# 01SignalDetect.net
KiCad netlist of a schematic drawn in Altium Designer
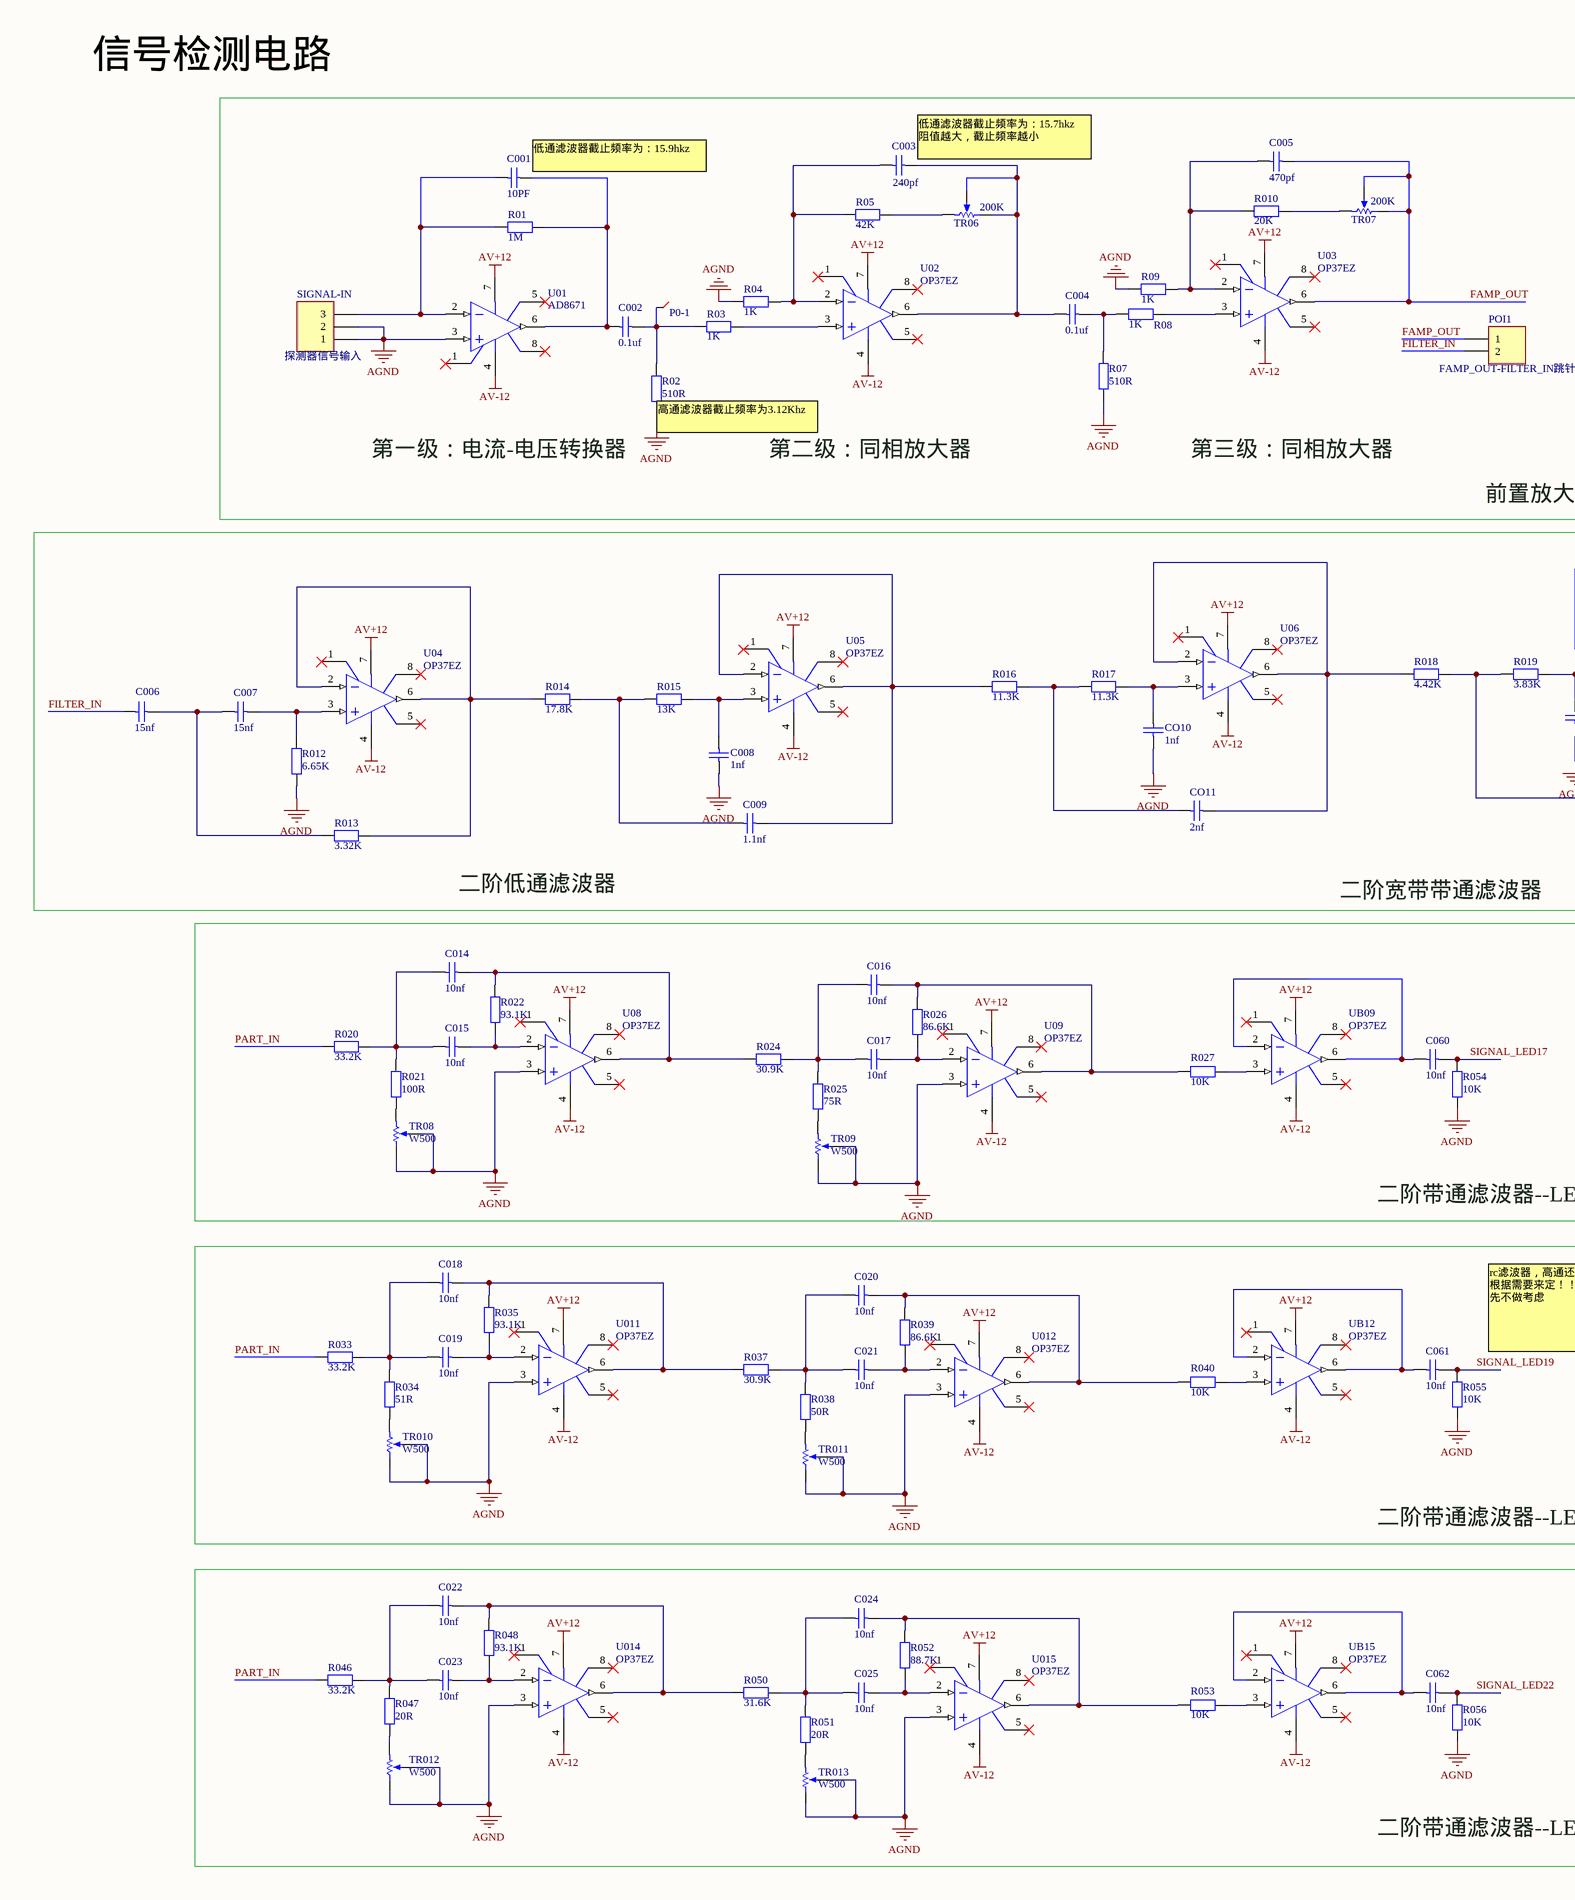
[diagram p0: 01SignalDetect.SchDoc, left]
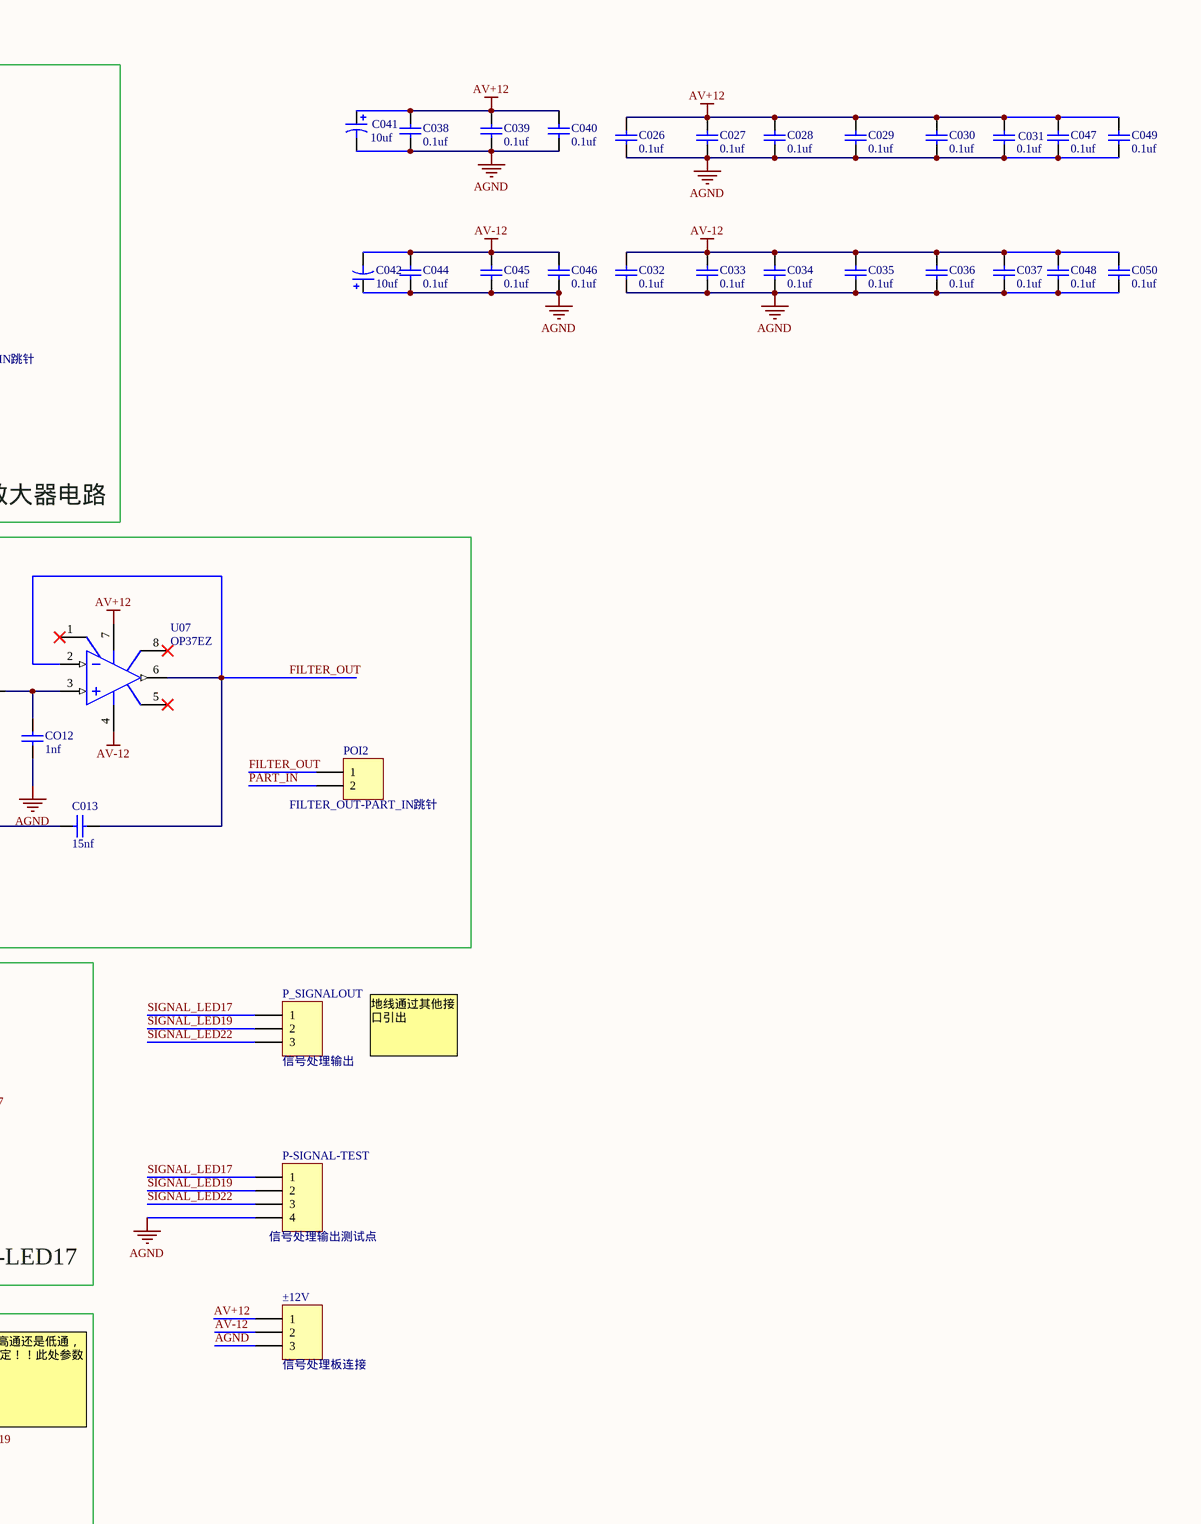
[diagram p1: 01SignalDetect.SchDoc, right]

(export (version "E")
  (design (tool "Eeschema 10.0.6"))
  (components
    (comp (ref "C001")
      (value "10PF")
      (footprint "CC0805")
      (description "Capacitor")
      (fields (field (name "Comment") "Cap") (field (name "PUBLISHER") "Altium Limited"))
      (libsource (lib "Miscellaneous Devices") (part "Cap"))
    )
    (comp (ref "C002")
      (value "0.1uf")
      (footprint "CC0805")
      (description "Capacitor")
      (fields (field (name "Comment") "Cap") (field (name "PUBLISHER") "Altium Limited"))
      (libsource (lib "Miscellaneous Devices") (part "Cap"))
    )
    (comp (ref "C003")
      (value "240pf")
      (footprint "CC0805")
      (description "Capacitor")
      (fields (field (name "Comment") "Cap") (field (name "PUBLISHER") "Altium Limited"))
      (libsource (lib "Miscellaneous Devices") (part "Cap"))
    )
    (comp (ref "C004")
      (value "0.1uf")
      (footprint "CC0805")
      (description "Capacitor")
      (fields (field (name "Comment") "Cap") (field (name "PUBLISHER") "Altium Limited"))
      (libsource (lib "Miscellaneous Devices") (part "Cap"))
    )
    (comp (ref "C005")
      (value "470pf")
      (footprint "CC0805")
      (description "Capacitor")
      (fields (field (name "Comment") "Cap") (field (name "PUBLISHER") "Altium Limited"))
      (libsource (lib "Miscellaneous Devices") (part "Cap"))
    )
    (comp (ref "C006")
      (value "15nf")
      (footprint "CC0805")
      (description "Capacitor")
      (fields (field (name "Comment") "Cap") (field (name "PUBLISHER") "Altium Limited"))
      (libsource (lib "Miscellaneous Devices") (part "Cap"))
    )
    (comp (ref "C007")
      (value "15nf")
      (footprint "CC0805")
      (description "Capacitor")
      (fields (field (name "Comment") "Cap") (field (name "PUBLISHER") "Altium Limited"))
      (libsource (lib "Miscellaneous Devices") (part "Cap"))
    )
    (comp (ref "C008")
      (value "1nf")
      (footprint "CC0805")
      (description "Capacitor")
      (fields (field (name "Comment") "Cap") (field (name "PUBLISHER") "Altium Limited"))
      (libsource (lib "Miscellaneous Devices") (part "Cap"))
    )
    (comp (ref "C009")
      (value "1.1nf")
      (footprint "CC0805")
      (description "Capacitor")
      (fields (field (name "Comment") "Cap") (field (name "PUBLISHER") "Altium Limited"))
      (libsource (lib "Miscellaneous Devices") (part "Cap"))
    )
    (comp (ref "C013")
      (value "15nf")
      (footprint "CC0805")
      (description "Capacitor")
      (fields (field (name "Comment") "Cap") (field (name "PUBLISHER") "Altium Limited"))
      (libsource (lib "Miscellaneous Devices") (part "Cap"))
    )
    (comp (ref "C014")
      (value "10nf")
      (footprint "校正电容")
      (description "Capacitor")
      (fields (field (name "Comment") "Cap") (field (name "PUBLISHER") "Altium Limited"))
      (libsource (lib "Miscellaneous Devices") (part "Cap"))
    )
    (comp (ref "C015")
      (value "10nf")
      (footprint "校正电容")
      (description "Capacitor")
      (fields (field (name "Comment") "Cap") (field (name "PUBLISHER") "Altium Limited"))
      (libsource (lib "Miscellaneous Devices") (part "Cap"))
    )
    (comp (ref "C016")
      (value "10nf")
      (footprint "校正电容")
      (description "Capacitor")
      (fields (field (name "Comment") "Cap") (field (name "PUBLISHER") "Altium Limited"))
      (libsource (lib "Miscellaneous Devices") (part "Cap"))
    )
    (comp (ref "C017")
      (value "10nf")
      (footprint "校正电容")
      (description "Capacitor")
      (fields (field (name "Comment") "Cap") (field (name "PUBLISHER") "Altium Limited"))
      (libsource (lib "Miscellaneous Devices") (part "Cap"))
    )
    (comp (ref "C018")
      (value "10nf")
      (footprint "校正电容")
      (description "Capacitor")
      (fields (field (name "Comment") "Cap") (field (name "PUBLISHER") "Altium Limited"))
      (libsource (lib "Miscellaneous Devices") (part "Cap"))
    )
    (comp (ref "C019")
      (value "10nf")
      (footprint "校正电容")
      (description "Capacitor")
      (fields (field (name "Comment") "Cap") (field (name "PUBLISHER") "Altium Limited"))
      (libsource (lib "Miscellaneous Devices") (part "Cap"))
    )
    (comp (ref "C020")
      (value "10nf")
      (footprint "校正电容")
      (description "Capacitor")
      (fields (field (name "Comment") "Cap") (field (name "PUBLISHER") "Altium Limited"))
      (libsource (lib "Miscellaneous Devices") (part "Cap"))
    )
    (comp (ref "C021")
      (value "10nf")
      (footprint "校正电容")
      (description "Capacitor")
      (fields (field (name "Comment") "Cap") (field (name "PUBLISHER") "Altium Limited"))
      (libsource (lib "Miscellaneous Devices") (part "Cap"))
    )
    (comp (ref "C022")
      (value "10nf")
      (footprint "校正电容")
      (description "Capacitor")
      (fields (field (name "Comment") "Cap") (field (name "PUBLISHER") "Altium Limited"))
      (libsource (lib "Miscellaneous Devices") (part "Cap"))
    )
    (comp (ref "C023")
      (value "10nf")
      (footprint "校正电容")
      (description "Capacitor")
      (fields (field (name "Comment") "Cap") (field (name "PUBLISHER") "Altium Limited"))
      (libsource (lib "Miscellaneous Devices") (part "Cap"))
    )
    (comp (ref "C024")
      (value "10nf")
      (footprint "校正电容")
      (description "Capacitor")
      (fields (field (name "Comment") "Cap") (field (name "PUBLISHER") "Altium Limited"))
      (libsource (lib "Miscellaneous Devices") (part "Cap"))
    )
    (comp (ref "C025")
      (value "10nf")
      (footprint "校正电容")
      (description "Capacitor")
      (fields (field (name "Comment") "Cap") (field (name "PUBLISHER") "Altium Limited"))
      (libsource (lib "Miscellaneous Devices") (part "Cap"))
    )
    (comp (ref "C026")
      (value "0.1uf")
      (footprint "CC0805")
      (description "Capacitor")
      (fields (field (name "Comment") "Cap") (field (name "PUBLISHER") "Altium Limited"))
      (libsource (lib "Miscellaneous Devices") (part "Cap"))
    )
    (comp (ref "C027")
      (value "0.1uf")
      (footprint "CC0805")
      (description "Capacitor")
      (fields (field (name "Comment") "Cap") (field (name "PUBLISHER") "Altium Limited"))
      (libsource (lib "Miscellaneous Devices") (part "Cap"))
    )
    (comp (ref "C028")
      (value "0.1uf")
      (footprint "CC0805")
      (description "Capacitor")
      (fields (field (name "Comment") "Cap") (field (name "PUBLISHER") "Altium Limited"))
      (libsource (lib "Miscellaneous Devices") (part "Cap"))
    )
    (comp (ref "C029")
      (value "0.1uf")
      (footprint "CC0805")
      (description "Capacitor")
      (fields (field (name "Comment") "Cap") (field (name "PUBLISHER") "Altium Limited"))
      (libsource (lib "Miscellaneous Devices") (part "Cap"))
    )
    (comp (ref "C030")
      (value "0.1uf")
      (footprint "CC0805")
      (description "Capacitor")
      (fields (field (name "Comment") "Cap") (field (name "PUBLISHER") "Altium Limited"))
      (libsource (lib "Miscellaneous Devices") (part "Cap"))
    )
    (comp (ref "C031")
      (value "0.1uf")
      (footprint "CC0805")
      (description "Capacitor")
      (fields (field (name "Comment") "Cap") (field (name "PUBLISHER") "Altium Limited"))
      (libsource (lib "Miscellaneous Devices") (part "Cap"))
    )
    (comp (ref "C032")
      (value "0.1uf")
      (footprint "CC0805")
      (description "Capacitor")
      (fields (field (name "Comment") "Cap") (field (name "PUBLISHER") "Altium Limited"))
      (libsource (lib "Miscellaneous Devices") (part "Cap"))
    )
    (comp (ref "C033")
      (value "0.1uf")
      (footprint "CC0805")
      (description "Capacitor")
      (fields (field (name "Comment") "Cap") (field (name "PUBLISHER") "Altium Limited"))
      (libsource (lib "Miscellaneous Devices") (part "Cap"))
    )
    (comp (ref "C034")
      (value "0.1uf")
      (footprint "CC0805")
      (description "Capacitor")
      (fields (field (name "Comment") "Cap") (field (name "PUBLISHER") "Altium Limited"))
      (libsource (lib "Miscellaneous Devices") (part "Cap"))
    )
    (comp (ref "C035")
      (value "0.1uf")
      (footprint "CC0805")
      (description "Capacitor")
      (fields (field (name "Comment") "Cap") (field (name "PUBLISHER") "Altium Limited"))
      (libsource (lib "Miscellaneous Devices") (part "Cap"))
    )
    (comp (ref "C036")
      (value "0.1uf")
      (footprint "CC0805")
      (description "Capacitor")
      (fields (field (name "Comment") "Cap") (field (name "PUBLISHER") "Altium Limited"))
      (libsource (lib "Miscellaneous Devices") (part "Cap"))
    )
    (comp (ref "C037")
      (value "0.1uf")
      (footprint "CC0805")
      (description "Capacitor")
      (fields (field (name "Comment") "Cap") (field (name "PUBLISHER") "Altium Limited"))
      (libsource (lib "Miscellaneous Devices") (part "Cap"))
    )
    (comp (ref "C038")
      (value "0.1uf")
      (footprint "CC0805")
      (description "Capacitor")
      (fields (field (name "Comment") "Cap") (field (name "PUBLISHER") "Altium Limited"))
      (libsource (lib "Miscellaneous Devices") (part "Cap"))
    )
    (comp (ref "C039")
      (value "0.1uf")
      (footprint "CC0805")
      (description "Capacitor")
      (fields (field (name "Comment") "Cap") (field (name "PUBLISHER") "Altium Limited"))
      (libsource (lib "Miscellaneous Devices") (part "Cap"))
    )
    (comp (ref "C040")
      (value "0.1uf")
      (footprint "CC0805")
      (description "Capacitor")
      (fields (field (name "Comment") "Cap") (field (name "PUBLISHER") "Altium Limited"))
      (libsource (lib "Miscellaneous Devices") (part "Cap"))
    )
    (comp (ref "C041")
      (value "10uf")
      (footprint "4*4.5 贴片电解电容")
      (description "Polarized Capacitor (Radial)")
      (fields (field (name "Comment") "Cap Pol1") (field (name "PUBLISHER") "Altium Limited"))
      (libsource (lib "Miscellaneous Devices") (part "Cap Pol1"))
    )
    (comp (ref "C042")
      (value "10uf")
      (footprint "4*4.5 贴片电解电容")
      (description "Polarized Capacitor (Radial)")
      (fields (field (name "Comment") "Cap Pol1") (field (name "PUBLISHER") "Altium Limited"))
      (libsource (lib "Miscellaneous Devices") (part "Cap Pol1"))
    )
    (comp (ref "C044")
      (value "0.1uf")
      (footprint "CC0805")
      (description "Capacitor")
      (fields (field (name "Comment") "Cap") (field (name "PUBLISHER") "Altium Limited"))
      (libsource (lib "Miscellaneous Devices") (part "Cap"))
    )
    (comp (ref "C045")
      (value "0.1uf")
      (footprint "CC0805")
      (description "Capacitor")
      (fields (field (name "Comment") "Cap") (field (name "PUBLISHER") "Altium Limited"))
      (libsource (lib "Miscellaneous Devices") (part "Cap"))
    )
    (comp (ref "C046")
      (value "0.1uf")
      (footprint "CC0805")
      (description "Capacitor")
      (fields (field (name "Comment") "Cap") (field (name "PUBLISHER") "Altium Limited"))
      (libsource (lib "Miscellaneous Devices") (part "Cap"))
    )
    (comp (ref "C047")
      (value "0.1uf")
      (footprint "CC0805")
      (description "Capacitor")
      (fields (field (name "Comment") "Cap") (field (name "PUBLISHER") "Altium Limited"))
      (libsource (lib "Miscellaneous Devices") (part "Cap"))
    )
    (comp (ref "C048")
      (value "0.1uf")
      (footprint "CC0805")
      (description "Capacitor")
      (fields (field (name "Comment") "Cap") (field (name "PUBLISHER") "Altium Limited"))
      (libsource (lib "Miscellaneous Devices") (part "Cap"))
    )
    (comp (ref "C049")
      (value "0.1uf")
      (footprint "CC0805")
      (description "Capacitor")
      (fields (field (name "Comment") "Cap") (field (name "PUBLISHER") "Altium Limited"))
      (libsource (lib "Miscellaneous Devices") (part "Cap"))
    )
    (comp (ref "C050")
      (value "0.1uf")
      (footprint "CC0805")
      (description "Capacitor")
      (fields (field (name "Comment") "Cap") (field (name "PUBLISHER") "Altium Limited"))
      (libsource (lib "Miscellaneous Devices") (part "Cap"))
    )
    (comp (ref "C060")
      (value "10nf")
      (footprint "CC0805")
      (description "Capacitor")
      (fields (field (name "Comment") "Cap") (field (name "PUBLISHER") "Altium Limited"))
      (libsource (lib "Miscellaneous Devices") (part "Cap"))
    )
    (comp (ref "C061")
      (value "10nf")
      (footprint "CC0805")
      (description "Capacitor")
      (fields (field (name "Comment") "Cap") (field (name "PUBLISHER") "Altium Limited"))
      (libsource (lib "Miscellaneous Devices") (part "Cap"))
    )
    (comp (ref "C062")
      (value "10nf")
      (footprint "CC0805")
      (description "Capacitor")
      (fields (field (name "Comment") "Cap") (field (name "PUBLISHER") "Altium Limited"))
      (libsource (lib "Miscellaneous Devices") (part "Cap"))
    )
    (comp (ref "CO10")
      (value "1nf")
      (footprint "CC0805")
      (description "Capacitor")
      (fields (field (name "Comment") "Cap") (field (name "PUBLISHER") "Altium Limited"))
      (libsource (lib "Miscellaneous Devices") (part "Cap"))
    )
    (comp (ref "CO11")
      (value "2nf")
      (footprint "CC0805")
      (description "Capacitor")
      (fields (field (name "Comment") "Cap") (field (name "PUBLISHER") "Altium Limited"))
      (libsource (lib "Miscellaneous Devices") (part "Cap"))
    )
    (comp (ref "CO12")
      (value "1nf")
      (footprint "CC0805")
      (description "Capacitor")
      (fields (field (name "Comment") "Cap") (field (name "PUBLISHER") "Altium Limited"))
      (libsource (lib "Miscellaneous Devices") (part "Cap"))
    )
    (comp (ref "P-SIGNAL-TEST")
      (value "信号处理输出测试点")
      (footprint "HDR1X4")
      (description "Header, 4-Pin")
      (fields (field (name "PUBLISHER") "Altium Limited"))
      (libsource (lib "Miscellaneous Connectors") (part "Header 4"))
    )
    (comp (ref "P0-1") (value "测试点") (footprint "Text_PAD") (libsource (lib "MY device0") (part "测试点")))
    (comp (ref "POI1")
      (value "FAMP_OUT-FILTER_IN跳针")
      (footprint "HDR1X2")
      (description "Header, 2-Pin")
      (fields (field (name "PUBLISHER") "Altium Limited"))
      (libsource (lib "Miscellaneous Connectors") (part "Header 2"))
    )
    (comp (ref "POI2")
      (value "FILTER_OUT-PART_IN跳针")
      (footprint "HDR1X2")
      (description "Header, 2-Pin")
      (fields (field (name "PUBLISHER") "Altium Limited"))
      (libsource (lib "Miscellaneous Connectors") (part "Header 2"))
    )
    (comp (ref "P_SIGNALOUT")
      (value "信号处理输出")
      (footprint "HDR1X3H")
      (description "Header, 3-Pin, Right Angle")
      (fields (field (name "PUBLISHER") "Altium Limited"))
      (libsource (lib "Miscellaneous Connectors") (part "Header 3H"))
    )
    (comp (ref "R01")
      (value "1M")
      (footprint "AXIAL-0.4")
      (description "Resistor")
      (fields (field (name "Comment") "Res2") (field (name "PUBLISHER") "Altium Limited"))
      (libsource (lib "") (part "Res2_1"))
    )
    (comp (ref "R02")
      (value "510R")
      (footprint "0805")
      (description "Resistor")
      (fields (field (name "Comment") "Res2") (field (name "PUBLISHER") "Altium Limited"))
      (libsource (lib "") (part "Res2_2"))
    )
    (comp (ref "R03")
      (value "1K")
      (footprint "0805")
      (description "Resistor")
      (fields (field (name "Comment") "Res2") (field (name "PUBLISHER") "Altium Limited"))
      (libsource (lib "") (part "Res2_1"))
    )
    (comp (ref "R04")
      (value "1K")
      (footprint "0805")
      (description "Resistor")
      (fields (field (name "Comment") "Res2") (field (name "PUBLISHER") "Altium Limited"))
      (libsource (lib "") (part "Res2_1"))
    )
    (comp (ref "R05")
      (value "42K")
      (footprint "0805")
      (description "Resistor")
      (fields (field (name "Comment") "Res2") (field (name "PUBLISHER") "Altium Limited"))
      (libsource (lib "") (part "Res2_1"))
    )
    (comp (ref "R07")
      (value "510R")
      (footprint "0805")
      (description "Resistor")
      (fields (field (name "Comment") "Res2") (field (name "PUBLISHER") "Altium Limited"))
      (libsource (lib "") (part "Res2_2"))
    )
    (comp (ref "R08")
      (value "1K")
      (footprint "0805")
      (description "Resistor")
      (fields (field (name "Comment") "Res2") (field (name "PUBLISHER") "Altium Limited"))
      (libsource (lib "") (part "Res2_1"))
    )
    (comp (ref "R09")
      (value "1K")
      (footprint "0805")
      (description "Resistor")
      (fields (field (name "Comment") "Res2") (field (name "PUBLISHER") "Altium Limited"))
      (libsource (lib "") (part "Res2_1"))
    )
    (comp (ref "R010")
      (value "20K")
      (footprint "0805")
      (description "Resistor")
      (fields (field (name "Comment") "Res2") (field (name "PUBLISHER") "Altium Limited"))
      (libsource (lib "") (part "Res2_1"))
    )
    (comp (ref "R012")
      (value "6.65K")
      (footprint "0805")
      (description "Resistor")
      (fields (field (name "Comment") "Res2") (field (name "PUBLISHER") "Altium Limited"))
      (libsource (lib "") (part "Res2_2"))
    )
    (comp (ref "R013")
      (value "3.32K")
      (footprint "0805")
      (description "Resistor")
      (fields (field (name "Comment") "Res2") (field (name "PUBLISHER") "Altium Limited"))
      (libsource (lib "") (part "Res2_3"))
    )
    (comp (ref "R014")
      (value "17.8K")
      (footprint "0805")
      (description "Resistor")
      (fields (field (name "Comment") "Res2") (field (name "PUBLISHER") "Altium Limited"))
      (libsource (lib "") (part "Res2_1"))
    )
    (comp (ref "R015")
      (value "13K")
      (footprint "0805")
      (description "Resistor")
      (fields (field (name "Comment") "Res2") (field (name "PUBLISHER") "Altium Limited"))
      (libsource (lib "") (part "Res2_3"))
    )
    (comp (ref "R016")
      (value "11.3K")
      (footprint "0805")
      (description "Resistor")
      (fields (field (name "Comment") "Res2") (field (name "PUBLISHER") "Altium Limited"))
      (libsource (lib "") (part "Res2_1"))
    )
    (comp (ref "R017")
      (value "11.3K")
      (footprint "0805")
      (description "Resistor")
      (fields (field (name "Comment") "Res2") (field (name "PUBLISHER") "Altium Limited"))
      (libsource (lib "") (part "Res2_1"))
    )
    (comp (ref "R018")
      (value "4.42K")
      (footprint "0805")
      (description "Resistor")
      (fields (field (name "Comment") "Res2") (field (name "PUBLISHER") "Altium Limited"))
      (libsource (lib "") (part "Res2_1"))
    )
    (comp (ref "R019")
      (value "3.83K")
      (footprint "0805")
      (description "Resistor")
      (fields (field (name "Comment") "Res2") (field (name "PUBLISHER") "Altium Limited"))
      (libsource (lib "") (part "Res2_1"))
    )
    (comp (ref "R020")
      (value "33.2K")
      (footprint "0805")
      (description "Resistor")
      (fields (field (name "Comment") "Res2") (field (name "PUBLISHER") "Altium Limited"))
      (libsource (lib "") (part "Res2_1"))
    )
    (comp (ref "R021")
      (value "100R")
      (footprint "0805")
      (description "Resistor")
      (fields (field (name "Comment") "Res2") (field (name "PUBLISHER") "Altium Limited"))
      (libsource (lib "") (part "Res2_2"))
    )
    (comp (ref "R022")
      (value "93.1K")
      (footprint "0805")
      (description "Resistor")
      (fields (field (name "Comment") "Res2") (field (name "PUBLISHER") "Altium Limited"))
      (libsource (lib "") (part "Res2_2"))
    )
    (comp (ref "R024")
      (value "30.9K")
      (footprint "0805")
      (description "Resistor")
      (fields (field (name "Comment") "Res2") (field (name "PUBLISHER") "Altium Limited"))
      (libsource (lib "") (part "Res2_1"))
    )
    (comp (ref "R025")
      (value "75R")
      (footprint "0805")
      (description "Resistor")
      (fields (field (name "Comment") "Res2") (field (name "PUBLISHER") "Altium Limited"))
      (libsource (lib "") (part "Res2_2"))
    )
    (comp (ref "R026")
      (value "86.6K")
      (footprint "0805")
      (description "Resistor")
      (fields (field (name "Comment") "Res2") (field (name "PUBLISHER") "Altium Limited"))
      (libsource (lib "") (part "Res2_2"))
    )
    (comp (ref "R027")
      (value "10K")
      (footprint "0805")
      (description "Resistor")
      (fields (field (name "Comment") "Res2") (field (name "PUBLISHER") "Altium Limited"))
      (libsource (lib "") (part "Res2_3"))
    )
    (comp (ref "R033")
      (value "33.2K")
      (footprint "0805")
      (description "Resistor")
      (fields (field (name "Comment") "Res2") (field (name "PUBLISHER") "Altium Limited"))
      (libsource (lib "") (part "Res2_1"))
    )
    (comp (ref "R034")
      (value "51R")
      (footprint "0805")
      (description "Resistor")
      (fields (field (name "Comment") "Res2") (field (name "PUBLISHER") "Altium Limited"))
      (libsource (lib "") (part "Res2_2"))
    )
    (comp (ref "R035")
      (value "93.1K")
      (footprint "0805")
      (description "Resistor")
      (fields (field (name "Comment") "Res2") (field (name "PUBLISHER") "Altium Limited"))
      (libsource (lib "") (part "Res2_2"))
    )
    (comp (ref "R037")
      (value "30.9K")
      (footprint "0805")
      (description "Resistor")
      (fields (field (name "Comment") "Res2") (field (name "PUBLISHER") "Altium Limited"))
      (libsource (lib "") (part "Res2_1"))
    )
    (comp (ref "R038")
      (value "50R")
      (footprint "0805")
      (description "Resistor")
      (fields (field (name "Comment") "Res2") (field (name "PUBLISHER") "Altium Limited"))
      (libsource (lib "") (part "Res2_2"))
    )
    (comp (ref "R039")
      (value "86.6K")
      (footprint "0805")
      (description "Resistor")
      (fields (field (name "Comment") "Res2") (field (name "PUBLISHER") "Altium Limited"))
      (libsource (lib "") (part "Res2_2"))
    )
    (comp (ref "R040")
      (value "10K")
      (footprint "0805")
      (description "Resistor")
      (fields (field (name "Comment") "Res2") (field (name "PUBLISHER") "Altium Limited"))
      (libsource (lib "") (part "Res2_3"))
    )
    (comp (ref "R046")
      (value "33.2K")
      (footprint "0805")
      (description "Resistor")
      (fields (field (name "Comment") "Res2") (field (name "PUBLISHER") "Altium Limited"))
      (libsource (lib "") (part "Res2_1"))
    )
    (comp (ref "R047")
      (value "20R")
      (footprint "0805")
      (description "Resistor")
      (fields (field (name "Comment") "Res2") (field (name "PUBLISHER") "Altium Limited"))
      (libsource (lib "") (part "Res2_2"))
    )
    (comp (ref "R048")
      (value "93.1K")
      (footprint "0805")
      (description "Resistor")
      (fields (field (name "Comment") "Res2") (field (name "PUBLISHER") "Altium Limited"))
      (libsource (lib "") (part "Res2_2"))
    )
    (comp (ref "R050")
      (value "31.6K")
      (footprint "0805")
      (description "Resistor")
      (fields (field (name "Comment") "Res2") (field (name "PUBLISHER") "Altium Limited"))
      (libsource (lib "") (part "Res2_1"))
    )
    (comp (ref "R051")
      (value "20R")
      (footprint "0805")
      (description "Resistor")
      (fields (field (name "Comment") "Res2") (field (name "PUBLISHER") "Altium Limited"))
      (libsource (lib "") (part "Res2_2"))
    )
    (comp (ref "R052")
      (value "88.7K")
      (footprint "0805")
      (description "Resistor")
      (fields (field (name "Comment") "Res2") (field (name "PUBLISHER") "Altium Limited"))
      (libsource (lib "") (part "Res2_2"))
    )
    (comp (ref "R053")
      (value "10K")
      (footprint "0805")
      (description "Resistor")
      (fields (field (name "Comment") "Res2") (field (name "PUBLISHER") "Altium Limited"))
      (libsource (lib "") (part "Res2_3"))
    )
    (comp (ref "R054")
      (value "10K")
      (footprint "0805")
      (description "Resistor")
      (fields (field (name "Comment") "Res2") (field (name "PUBLISHER") "Altium Limited"))
      (libsource (lib "Miscellaneous Devices") (part "Res2"))
    )
    (comp (ref "R055")
      (value "10K")
      (footprint "0805")
      (description "Resistor")
      (fields (field (name "Comment") "Res2") (field (name "PUBLISHER") "Altium Limited"))
      (libsource (lib "Miscellaneous Devices") (part "Res2"))
    )
    (comp (ref "R056")
      (value "10K")
      (footprint "0805")
      (description "Resistor")
      (fields (field (name "Comment") "Res2") (field (name "PUBLISHER") "Altium Limited"))
      (libsource (lib "Miscellaneous Devices") (part "Res2"))
    )
    (comp (ref "SIGNAL-IN")
      (value "探测器信号输入")
      (footprint "HDR1X3H")
      (description "Header, 3-Pin, Right Angle")
      (fields (field (name "PUBLISHER") "Altium Limited"))
      (libsource (lib "") (part "Header 3H_1"))
    )
    (comp (ref "TR06")
      (value "200K")
      (footprint "VR5")
      (description "Potentiometer")
      (fields (field (name "Comment") "RPot") (field (name "PUBLISHER") "Altium Limited"))
      (libsource (lib "Miscellaneous Devices") (part "RPot"))
    )
    (comp (ref "TR07")
      (value "200K")
      (footprint "VR5")
      (description "Potentiometer")
      (fields (field (name "Comment") "RPot") (field (name "PUBLISHER") "Altium Limited"))
      (libsource (lib "Miscellaneous Devices") (part "RPot"))
    )
    (comp (ref "TR08")
      (value "W500")
      (footprint "VR5")
      (description "Potentiometer")
      (fields (field (name "Comment") "RPot") (field (name "PUBLISHER") "Altium Limited"))
      (libsource (lib "Miscellaneous Devices") (part "RPot"))
    )
    (comp (ref "TR09")
      (value "W500")
      (footprint "VR5")
      (description "Potentiometer")
      (fields (field (name "Comment") "RPot") (field (name "PUBLISHER") "Altium Limited"))
      (libsource (lib "Miscellaneous Devices") (part "RPot"))
    )
    (comp (ref "TR010")
      (value "W500")
      (footprint "VR5")
      (description "Potentiometer")
      (fields (field (name "Comment") "RPot") (field (name "PUBLISHER") "Altium Limited"))
      (libsource (lib "Miscellaneous Devices") (part "RPot"))
    )
    (comp (ref "TR011")
      (value "W500")
      (footprint "VR5")
      (description "Potentiometer")
      (fields (field (name "Comment") "RPot") (field (name "PUBLISHER") "Altium Limited"))
      (libsource (lib "Miscellaneous Devices") (part "RPot"))
    )
    (comp (ref "TR012")
      (value "W500")
      (footprint "VR5")
      (description "Potentiometer")
      (fields (field (name "Comment") "RPot") (field (name "PUBLISHER") "Altium Limited"))
      (libsource (lib "Miscellaneous Devices") (part "RPot"))
    )
    (comp (ref "TR013")
      (value "W500")
      (footprint "VR5")
      (description "Potentiometer")
      (fields (field (name "Comment") "RPot") (field (name "PUBLISHER") "Altium Limited"))
      (libsource (lib "Miscellaneous Devices") (part "RPot"))
    )
    (comp (ref "U01")
      (value "AD8671")
      (footprint "SO-8-N")
      (description "Low-Noise, Precision Operational Amplifier")
      (fields (field (name "PUBLISHER") "Altium Limited"))
      (libsource (lib "AD Operational Amplifier") (part "OP27FJ"))
    )
    (comp (ref "U02")
      (value "OP37EZ")
      (footprint "SO-8-N")
      (description "Low-Noise, Precision, High-Speed Operational Amplifier (Avcl >= 5)")
      (fields (field (name "PUBLISHER") "Altium Limited"))
      (libsource (lib "AD Operational Amplifier") (part "OP37EZ"))
    )
    (comp (ref "U03")
      (value "OP37EZ")
      (footprint "SO-8-N")
      (description "Low-Noise, Precision, High-Speed Operational Amplifier (Avcl >= 5)")
      (fields (field (name "PUBLISHER") "Altium Limited"))
      (libsource (lib "AD Operational Amplifier") (part "OP37EZ"))
    )
    (comp (ref "U04")
      (value "OP37EZ")
      (footprint "SO-8-N")
      (description "Low-Noise, Precision, High-Speed Operational Amplifier (Avcl >= 5)")
      (fields (field (name "PUBLISHER") "Altium Limited"))
      (libsource (lib "AD Operational Amplifier") (part "OP37EZ"))
    )
    (comp (ref "U05")
      (value "OP37EZ")
      (footprint "SO-8-N")
      (description "Low-Noise, Precision, High-Speed Operational Amplifier (Avcl >= 5)")
      (fields (field (name "PUBLISHER") "Altium Limited"))
      (libsource (lib "AD Operational Amplifier") (part "OP37EZ"))
    )
    (comp (ref "U06")
      (value "OP37EZ")
      (footprint "SO-8-N")
      (description "Low-Noise, Precision, High-Speed Operational Amplifier (Avcl >= 5)")
      (fields (field (name "PUBLISHER") "Altium Limited"))
      (libsource (lib "AD Operational Amplifier") (part "OP37EZ"))
    )
    (comp (ref "U07")
      (value "OP37EZ")
      (footprint "SO-8-N")
      (description "Low-Noise, Precision, High-Speed Operational Amplifier (Avcl >= 5)")
      (fields (field (name "PUBLISHER") "Altium Limited"))
      (libsource (lib "AD Operational Amplifier") (part "OP37EZ"))
    )
    (comp (ref "U08")
      (value "OP37EZ")
      (footprint "SO-8-N")
      (description "Low-Noise, Precision, High-Speed Operational Amplifier (Avcl >= 5)")
      (fields (field (name "PUBLISHER") "Altium Limited"))
      (libsource (lib "AD Operational Amplifier") (part "OP37EZ"))
    )
    (comp (ref "U09")
      (value "OP37EZ")
      (footprint "SO-8-N")
      (description "Low-Noise, Precision, High-Speed Operational Amplifier (Avcl >= 5)")
      (fields (field (name "PUBLISHER") "Altium Limited"))
      (libsource (lib "AD Operational Amplifier") (part "OP37EZ"))
    )
    (comp (ref "U011")
      (value "OP37EZ")
      (footprint "SO-8-N")
      (description "Low-Noise, Precision, High-Speed Operational Amplifier (Avcl >= 5)")
      (fields (field (name "PUBLISHER") "Altium Limited"))
      (libsource (lib "AD Operational Amplifier") (part "OP37EZ"))
    )
    (comp (ref "U012")
      (value "OP37EZ")
      (footprint "SO-8-N")
      (description "Low-Noise, Precision, High-Speed Operational Amplifier (Avcl >= 5)")
      (fields (field (name "PUBLISHER") "Altium Limited"))
      (libsource (lib "AD Operational Amplifier") (part "OP37EZ"))
    )
    (comp (ref "U014")
      (value "OP37EZ")
      (footprint "SO-8-N")
      (description "Low-Noise, Precision, High-Speed Operational Amplifier (Avcl >= 5)")
      (fields (field (name "PUBLISHER") "Altium Limited"))
      (libsource (lib "AD Operational Amplifier") (part "OP37EZ"))
    )
    (comp (ref "U015")
      (value "OP37EZ")
      (footprint "SO-8-N")
      (description "Low-Noise, Precision, High-Speed Operational Amplifier (Avcl >= 5)")
      (fields (field (name "PUBLISHER") "Altium Limited"))
      (libsource (lib "AD Operational Amplifier") (part "OP37EZ"))
    )
    (comp (ref "UB09")
      (value "OP37EZ")
      (footprint "SO-8-N")
      (description "Low-Noise, Precision, High-Speed Operational Amplifier (Avcl >= 5)")
      (fields (field (name "PUBLISHER") "Altium Limited"))
      (libsource (lib "AD Operational Amplifier") (part "OP37EZ"))
    )
    (comp (ref "UB12")
      (value "OP37EZ")
      (footprint "SO-8-N")
      (description "Low-Noise, Precision, High-Speed Operational Amplifier (Avcl >= 5)")
      (fields (field (name "PUBLISHER") "Altium Limited"))
      (libsource (lib "AD Operational Amplifier") (part "OP37EZ"))
    )
    (comp (ref "UB15")
      (value "OP37EZ")
      (footprint "SO-8-N")
      (description "Low-Noise, Precision, High-Speed Operational Amplifier (Avcl >= 5)")
      (fields (field (name "PUBLISHER") "Altium Limited"))
      (libsource (lib "AD Operational Amplifier") (part "OP37EZ"))
    )
    (comp (ref "±12V")
      (value "信号处理板连接")
      (footprint "HDR1X3H")
      (description "Header, 3-Pin, Right Angle")
      (fields (field (name "PUBLISHER") "Altium Limited"))
      (libsource (lib "Miscellaneous Connectors") (part "Header 3H"))
    )
  )
  (nets
    (net (code "1") (name "/FAMP_OUT") (class "Default")
      (node (ref "C005") (pin "1") (pinfunction "1_1") (pintype "passive"))
      (node (ref "POI1") (pin "1") (pinfunction "1_1") (pintype "passive"))
      (node (ref "TR07") (pin "1") (pinfunction "TOP_1") (pintype "passive"))
      (node (ref "TR07") (pin "2") (pinfunction "TAP_2") (pintype "passive"))
      (node (ref "U03") (pin "6") (pinfunction "OUT_6") (pintype "output"))
    )
    (net (code "2") (name "/FILTER_IN") (class "Default")
      (node (ref "C006") (pin "2") (pinfunction "2_2") (pintype "passive"))
      (node (ref "POI1") (pin "2") (pinfunction "2_2") (pintype "passive"))
    )
    (net (code "3") (name "/FILTER_OUT") (class "Default")
      (node (ref "C013") (pin "1") (pinfunction "1_1") (pintype "passive"))
      (node (ref "POI2") (pin "1") (pinfunction "1_1") (pintype "passive"))
      (node (ref "U07") (pin "2") (pinfunction "IN-_2") (pintype "input"))
      (node (ref "U07") (pin "6") (pinfunction "OUT_6") (pintype "output"))
    )
    (net (code "4") (name "/PART_IN") (class "Default")
      (node (ref "POI2") (pin "2") (pinfunction "2_2") (pintype "passive"))
      (node (ref "R020") (pin "1") (pinfunction "1_1") (pintype "passive"))
      (node (ref "R033") (pin "1") (pinfunction "1_1") (pintype "passive"))
      (node (ref "R046") (pin "1") (pinfunction "1_1") (pintype "passive"))
    )
    (net (code "5") (name "/SIGNAL_LED17") (class "Default")
      (node (ref "C060") (pin "2") (pinfunction "2_2") (pintype "passive"))
      (node (ref "P-SIGNAL-TEST") (pin "1") (pinfunction "1_1") (pintype "passive"))
      (node (ref "P_SIGNALOUT") (pin "1") (pinfunction "1_1") (pintype "passive"))
      (node (ref "R054") (pin "1") (pinfunction "1_1") (pintype "passive"))
    )
    (net (code "6") (name "/SIGNAL_LED19") (class "Default")
      (node (ref "C061") (pin "2") (pinfunction "2_2") (pintype "passive"))
      (node (ref "P-SIGNAL-TEST") (pin "2") (pinfunction "2_2") (pintype "passive"))
      (node (ref "P_SIGNALOUT") (pin "2") (pinfunction "2_2") (pintype "passive"))
      (node (ref "R055") (pin "1") (pinfunction "1_1") (pintype "passive"))
    )
    (net (code "7") (name "/SIGNAL_LED22") (class "Default")
      (node (ref "C062") (pin "2") (pinfunction "2_2") (pintype "passive"))
      (node (ref "P-SIGNAL-TEST") (pin "3") (pinfunction "3_3") (pintype "passive"))
      (node (ref "P_SIGNALOUT") (pin "3") (pinfunction "3_3") (pintype "passive"))
      (node (ref "R056") (pin "1") (pinfunction "1_1") (pintype "passive"))
    )
    (net (code "8") (name "AGND") (class "Default")
      (node (ref "C008") (pin "2") (pinfunction "2_2") (pintype "passive"))
      (node (ref "C026") (pin "2") (pinfunction "2_2") (pintype "passive"))
      (node (ref "C027") (pin "2") (pinfunction "2_2") (pintype "passive"))
      (node (ref "C028") (pin "2") (pinfunction "2_2") (pintype "passive"))
      (node (ref "C029") (pin "2") (pinfunction "2_2") (pintype "passive"))
      (node (ref "C030") (pin "2") (pinfunction "2_2") (pintype "passive"))
      (node (ref "C031") (pin "2") (pinfunction "2_2") (pintype "passive"))
      (node (ref "C032") (pin "2") (pinfunction "2_2") (pintype "passive"))
      (node (ref "C033") (pin "2") (pinfunction "2_2") (pintype "passive"))
      (node (ref "C034") (pin "2") (pinfunction "2_2") (pintype "passive"))
      (node (ref "C035") (pin "2") (pinfunction "2_2") (pintype "passive"))
      (node (ref "C036") (pin "2") (pinfunction "2_2") (pintype "passive"))
      (node (ref "C037") (pin "2") (pinfunction "2_2") (pintype "passive"))
      (node (ref "C038") (pin "2") (pinfunction "2_2") (pintype "passive"))
      (node (ref "C039") (pin "2") (pinfunction "2_2") (pintype "passive"))
      (node (ref "C040") (pin "2") (pinfunction "2_2") (pintype "passive"))
      (node (ref "C041") (pin "2") (pinfunction "2_2") (pintype "passive"))
      (node (ref "C042") (pin "1") (pinfunction "1_1") (pintype "passive"))
      (node (ref "C044") (pin "2") (pinfunction "2_2") (pintype "passive"))
      (node (ref "C045") (pin "2") (pinfunction "2_2") (pintype "passive"))
      (node (ref "C046") (pin "2") (pinfunction "2_2") (pintype "passive"))
      (node (ref "C047") (pin "2") (pinfunction "2_2") (pintype "passive"))
      (node (ref "C048") (pin "2") (pinfunction "2_2") (pintype "passive"))
      (node (ref "C049") (pin "2") (pinfunction "2_2") (pintype "passive"))
      (node (ref "C050") (pin "2") (pinfunction "2_2") (pintype "passive"))
      (node (ref "CO10") (pin "1") (pinfunction "1_1") (pintype "passive"))
      (node (ref "CO12") (pin "1") (pinfunction "1_1") (pintype "passive"))
      (node (ref "P-SIGNAL-TEST") (pin "4") (pinfunction "4_4") (pintype "passive"))
      (node (ref "R012") (pin "1") (pinfunction "1_1") (pintype "passive"))
      (node (ref "R02") (pin "1") (pinfunction "1_1") (pintype "passive"))
      (node (ref "R04") (pin "1") (pinfunction "1_1") (pintype "passive"))
      (node (ref "R054") (pin "2") (pinfunction "2_2") (pintype "passive"))
      (node (ref "R055") (pin "2") (pinfunction "2_2") (pintype "passive"))
      (node (ref "R056") (pin "2") (pinfunction "2_2") (pintype "passive"))
      (node (ref "R07") (pin "1") (pinfunction "1_1") (pintype "passive"))
      (node (ref "R09") (pin "1") (pinfunction "1_1") (pintype "passive"))
      (node (ref "SIGNAL-IN") (pin "1") (pinfunction "1_1") (pintype "passive"))
      (node (ref "SIGNAL-IN") (pin "2") (pinfunction "2_2") (pintype "passive"))
      (node (ref "TR010") (pin "1") (pinfunction "TOP_1") (pintype "passive"))
      (node (ref "TR010") (pin "2") (pinfunction "TAP_2") (pintype "passive"))
      (node (ref "TR011") (pin "1") (pinfunction "TOP_1") (pintype "passive"))
      (node (ref "TR011") (pin "2") (pinfunction "TAP_2") (pintype "passive"))
      (node (ref "TR012") (pin "1") (pinfunction "TOP_1") (pintype "passive"))
      (node (ref "TR012") (pin "2") (pinfunction "TAP_2") (pintype "passive"))
      (node (ref "TR013") (pin "1") (pinfunction "TOP_1") (pintype "passive"))
      (node (ref "TR013") (pin "2") (pinfunction "TAP_2") (pintype "passive"))
      (node (ref "TR08") (pin "1") (pinfunction "TOP_1") (pintype "passive"))
      (node (ref "TR08") (pin "2") (pinfunction "TAP_2") (pintype "passive"))
      (node (ref "TR09") (pin "1") (pinfunction "TOP_1") (pintype "passive"))
      (node (ref "TR09") (pin "2") (pinfunction "TAP_2") (pintype "passive"))
      (node (ref "U01") (pin "3") (pinfunction "IN+_3") (pintype "input"))
      (node (ref "U011") (pin "3") (pinfunction "IN+_3") (pintype "input"))
      (node (ref "U012") (pin "3") (pinfunction "IN+_3") (pintype "input"))
      (node (ref "U014") (pin "3") (pinfunction "IN+_3") (pintype "input"))
      (node (ref "U015") (pin "3") (pinfunction "IN+_3") (pintype "input"))
      (node (ref "U08") (pin "3") (pinfunction "IN+_3") (pintype "input"))
      (node (ref "U09") (pin "3") (pinfunction "IN+_3") (pintype "input"))
      (node (ref "±12V") (pin "3") (pinfunction "3_3") (pintype "passive"))
    )
    (net (code "9") (name "AV+12") (class "Default")
      (node (ref "C026") (pin "1") (pinfunction "1_1") (pintype "passive"))
      (node (ref "C027") (pin "1") (pinfunction "1_1") (pintype "passive"))
      (node (ref "C028") (pin "1") (pinfunction "1_1") (pintype "passive"))
      (node (ref "C029") (pin "1") (pinfunction "1_1") (pintype "passive"))
      (node (ref "C030") (pin "1") (pinfunction "1_1") (pintype "passive"))
      (node (ref "C031") (pin "1") (pinfunction "1_1") (pintype "passive"))
      (node (ref "C038") (pin "1") (pinfunction "1_1") (pintype "passive"))
      (node (ref "C039") (pin "1") (pinfunction "1_1") (pintype "passive"))
      (node (ref "C040") (pin "1") (pinfunction "1_1") (pintype "passive"))
      (node (ref "C041") (pin "1") (pinfunction "1_1") (pintype "passive"))
      (node (ref "C047") (pin "1") (pinfunction "1_1") (pintype "passive"))
      (node (ref "C049") (pin "1") (pinfunction "1_1") (pintype "passive"))
      (node (ref "U01") (pin "7") (pinfunction "V+_7") (pintype "power_in"))
      (node (ref "U011") (pin "7") (pinfunction "V+_7") (pintype "power_in"))
      (node (ref "U012") (pin "7") (pinfunction "V+_7") (pintype "power_in"))
      (node (ref "U014") (pin "7") (pinfunction "V+_7") (pintype "power_in"))
      (node (ref "U015") (pin "7") (pinfunction "V+_7") (pintype "power_in"))
      (node (ref "U02") (pin "7") (pinfunction "V+_7") (pintype "power_in"))
      (node (ref "U03") (pin "7") (pinfunction "V+_7") (pintype "power_in"))
      (node (ref "U04") (pin "7") (pinfunction "V+_7") (pintype "power_in"))
      (node (ref "U05") (pin "7") (pinfunction "V+_7") (pintype "power_in"))
      (node (ref "U06") (pin "7") (pinfunction "V+_7") (pintype "power_in"))
      (node (ref "U07") (pin "7") (pinfunction "V+_7") (pintype "power_in"))
      (node (ref "U08") (pin "7") (pinfunction "V+_7") (pintype "power_in"))
      (node (ref "U09") (pin "7") (pinfunction "V+_7") (pintype "power_in"))
      (node (ref "UB09") (pin "7") (pinfunction "V+_7") (pintype "power_in"))
      (node (ref "UB12") (pin "7") (pinfunction "V+_7") (pintype "power_in"))
      (node (ref "UB15") (pin "7") (pinfunction "V+_7") (pintype "power_in"))
      (node (ref "±12V") (pin "1") (pinfunction "1_1") (pintype "passive"))
    )
    (net (code "10") (name "AV-12") (class "Default")
      (node (ref "C032") (pin "1") (pinfunction "1_1") (pintype "passive"))
      (node (ref "C033") (pin "1") (pinfunction "1_1") (pintype "passive"))
      (node (ref "C034") (pin "1") (pinfunction "1_1") (pintype "passive"))
      (node (ref "C035") (pin "1") (pinfunction "1_1") (pintype "passive"))
      (node (ref "C036") (pin "1") (pinfunction "1_1") (pintype "passive"))
      (node (ref "C037") (pin "1") (pinfunction "1_1") (pintype "passive"))
      (node (ref "C042") (pin "2") (pinfunction "2_2") (pintype "passive"))
      (node (ref "C044") (pin "1") (pinfunction "1_1") (pintype "passive"))
      (node (ref "C045") (pin "1") (pinfunction "1_1") (pintype "passive"))
      (node (ref "C046") (pin "1") (pinfunction "1_1") (pintype "passive"))
      (node (ref "C048") (pin "1") (pinfunction "1_1") (pintype "passive"))
      (node (ref "C050") (pin "1") (pinfunction "1_1") (pintype "passive"))
      (node (ref "U01") (pin "4") (pinfunction "V-_4") (pintype "power_in"))
      (node (ref "U011") (pin "4") (pinfunction "V-_4") (pintype "power_in"))
      (node (ref "U012") (pin "4") (pinfunction "V-_4") (pintype "power_in"))
      (node (ref "U014") (pin "4") (pinfunction "V-_4") (pintype "power_in"))
      (node (ref "U015") (pin "4") (pinfunction "V-_4") (pintype "power_in"))
      (node (ref "U02") (pin "4") (pinfunction "V-_4") (pintype "power_in"))
      (node (ref "U03") (pin "4") (pinfunction "V-_4") (pintype "power_in"))
      (node (ref "U04") (pin "4") (pinfunction "V-_4") (pintype "power_in"))
      (node (ref "U05") (pin "4") (pinfunction "V-_4") (pintype "power_in"))
      (node (ref "U06") (pin "4") (pinfunction "V-_4") (pintype "power_in"))
      (node (ref "U07") (pin "4") (pinfunction "V-_4") (pintype "power_in"))
      (node (ref "U08") (pin "4") (pinfunction "V-_4") (pintype "power_in"))
      (node (ref "U09") (pin "4") (pinfunction "V-_4") (pintype "power_in"))
      (node (ref "UB09") (pin "4") (pinfunction "V-_4") (pintype "power_in"))
      (node (ref "UB12") (pin "4") (pinfunction "V-_4") (pintype "power_in"))
      (node (ref "UB15") (pin "4") (pinfunction "V-_4") (pintype "power_in"))
      (node (ref "±12V") (pin "2") (pinfunction "2_2") (pintype "passive"))
    )
    (net (code "11") (name "Net-(C002-Pad1)") (class "Default")
      (node (ref "C002") (pin "1") (pinfunction "1_1") (pintype "passive"))
      (node (ref "P0-1") (pin "0") (pinfunction "0_0") (pintype "passive"))
      (node (ref "R02") (pin "2") (pinfunction "2_2") (pintype "passive"))
      (node (ref "R03") (pin "1") (pinfunction "1_1") (pintype "passive"))
    )
    (net (code "12") (name "Net-(C004-Pad1)") (class "Default")
      (node (ref "C004") (pin "1") (pinfunction "1_1") (pintype "passive"))
      (node (ref "R07") (pin "2") (pinfunction "2_2") (pintype "passive"))
      (node (ref "R08") (pin "1") (pinfunction "1_1") (pintype "passive"))
    )
    (net (code "13") (name "Net-(C006-Pad1)") (class "Default")
      (node (ref "C006") (pin "1") (pinfunction "1_1") (pintype "passive"))
      (node (ref "C007") (pin "2") (pinfunction "2_2") (pintype "passive"))
      (node (ref "R013") (pin "2") (pinfunction "2_2") (pintype "passive"))
    )
    (net (code "14") (name "Net-(C009-Pad2)") (class "Default")
      (node (ref "C009") (pin "2") (pinfunction "2_2") (pintype "passive"))
      (node (ref "R014") (pin "2") (pinfunction "2_2") (pintype "passive"))
      (node (ref "R015") (pin "2") (pinfunction "2_2") (pintype "passive"))
    )
    (net (code "15") (name "Net-(C013-Pad2)") (class "Default")
      (node (ref "C013") (pin "2") (pinfunction "2_2") (pintype "passive"))
      (node (ref "R018") (pin "2") (pinfunction "2_2") (pintype "passive"))
      (node (ref "R019") (pin "1") (pinfunction "1_1") (pintype "passive"))
    )
    (net (code "16") (name "Net-(C014-Pad2)") (class "Default")
      (node (ref "C014") (pin "2") (pinfunction "2_2") (pintype "passive"))
      (node (ref "C015") (pin "2") (pinfunction "2_2") (pintype "passive"))
      (node (ref "R020") (pin "2") (pinfunction "2_2") (pintype "passive"))
      (node (ref "R021") (pin "2") (pinfunction "2_2") (pintype "passive"))
    )
    (net (code "17") (name "Net-(C016-Pad2)") (class "Default")
      (node (ref "C016") (pin "2") (pinfunction "2_2") (pintype "passive"))
      (node (ref "C017") (pin "2") (pinfunction "2_2") (pintype "passive"))
      (node (ref "R024") (pin "2") (pinfunction "2_2") (pintype "passive"))
      (node (ref "R025") (pin "2") (pinfunction "2_2") (pintype "passive"))
    )
    (net (code "18") (name "Net-(C018-Pad2)") (class "Default")
      (node (ref "C018") (pin "2") (pinfunction "2_2") (pintype "passive"))
      (node (ref "C019") (pin "2") (pinfunction "2_2") (pintype "passive"))
      (node (ref "R033") (pin "2") (pinfunction "2_2") (pintype "passive"))
      (node (ref "R034") (pin "2") (pinfunction "2_2") (pintype "passive"))
    )
    (net (code "19") (name "Net-(C020-Pad2)") (class "Default")
      (node (ref "C020") (pin "2") (pinfunction "2_2") (pintype "passive"))
      (node (ref "C021") (pin "2") (pinfunction "2_2") (pintype "passive"))
      (node (ref "R037") (pin "2") (pinfunction "2_2") (pintype "passive"))
      (node (ref "R038") (pin "2") (pinfunction "2_2") (pintype "passive"))
    )
    (net (code "20") (name "Net-(C022-Pad2)") (class "Default")
      (node (ref "C022") (pin "2") (pinfunction "2_2") (pintype "passive"))
      (node (ref "C023") (pin "2") (pinfunction "2_2") (pintype "passive"))
      (node (ref "R046") (pin "2") (pinfunction "2_2") (pintype "passive"))
      (node (ref "R047") (pin "2") (pinfunction "2_2") (pintype "passive"))
    )
    (net (code "21") (name "Net-(C024-Pad2)") (class "Default")
      (node (ref "C024") (pin "2") (pinfunction "2_2") (pintype "passive"))
      (node (ref "C025") (pin "2") (pinfunction "2_2") (pintype "passive"))
      (node (ref "R050") (pin "2") (pinfunction "2_2") (pintype "passive"))
      (node (ref "R051") (pin "2") (pinfunction "2_2") (pintype "passive"))
    )
    (net (code "22") (name "Net-(CO11-Pad2)") (class "Default")
      (node (ref "CO11") (pin "2") (pinfunction "2_2") (pintype "passive"))
      (node (ref "R016") (pin "2") (pinfunction "2_2") (pintype "passive"))
      (node (ref "R017") (pin "1") (pinfunction "1_1") (pintype "passive"))
    )
    (net (code "23") (name "Net-(TR06-BOT)") (class "Default")
      (node (ref "R05") (pin "2") (pinfunction "2_2") (pintype "passive"))
      (node (ref "TR06") (pin "3") (pinfunction "BOT_3") (pintype "passive"))
    )
    (net (code "24") (name "Net-(TR06-TAP)") (class "Default")
      (node (ref "C003") (pin "1") (pinfunction "1_1") (pintype "passive"))
      (node (ref "C004") (pin "2") (pinfunction "2_2") (pintype "passive"))
      (node (ref "TR06") (pin "1") (pinfunction "TOP_1") (pintype "passive"))
      (node (ref "TR06") (pin "2") (pinfunction "TAP_2") (pintype "passive"))
      (node (ref "U02") (pin "6") (pinfunction "OUT_6") (pintype "output"))
    )
    (net (code "25") (name "Net-(TR07-BOT)") (class "Default")
      (node (ref "R010") (pin "2") (pinfunction "2_2") (pintype "passive"))
      (node (ref "TR07") (pin "3") (pinfunction "BOT_3") (pintype "passive"))
    )
    (net (code "26") (name "Net-(TR08-BOT)") (class "Default")
      (node (ref "R021") (pin "1") (pinfunction "1_1") (pintype "passive"))
      (node (ref "TR08") (pin "3") (pinfunction "BOT_3") (pintype "passive"))
    )
    (net (code "27") (name "Net-(TR09-BOT)") (class "Default")
      (node (ref "R025") (pin "1") (pinfunction "1_1") (pintype "passive"))
      (node (ref "TR09") (pin "3") (pinfunction "BOT_3") (pintype "passive"))
    )
    (net (code "28") (name "Net-(TR010-BOT)") (class "Default")
      (node (ref "R034") (pin "1") (pinfunction "1_1") (pintype "passive"))
      (node (ref "TR010") (pin "3") (pinfunction "BOT_3") (pintype "passive"))
    )
    (net (code "29") (name "Net-(TR011-BOT)") (class "Default")
      (node (ref "R038") (pin "1") (pinfunction "1_1") (pintype "passive"))
      (node (ref "TR011") (pin "3") (pinfunction "BOT_3") (pintype "passive"))
    )
    (net (code "30") (name "Net-(TR012-BOT)") (class "Default")
      (node (ref "R047") (pin "1") (pinfunction "1_1") (pintype "passive"))
      (node (ref "TR012") (pin "3") (pinfunction "BOT_3") (pintype "passive"))
    )
    (net (code "31") (name "Net-(TR013-BOT)") (class "Default")
      (node (ref "R051") (pin "1") (pinfunction "1_1") (pintype "passive"))
      (node (ref "TR013") (pin "3") (pinfunction "BOT_3") (pintype "passive"))
    )
    (net (code "32") (name "Net-(U01-IN-)") (class "Default")
      (node (ref "C001") (pin "2") (pinfunction "2_2") (pintype "passive"))
      (node (ref "R01") (pin "1") (pinfunction "1_1") (pintype "passive"))
      (node (ref "SIGNAL-IN") (pin "3") (pinfunction "3_3") (pintype "passive"))
      (node (ref "U01") (pin "2") (pinfunction "IN-_2") (pintype "input"))
    )
    (net (code "33") (name "Net-(U01-OUT)") (class "Default")
      (node (ref "C001") (pin "1") (pinfunction "1_1") (pintype "passive"))
      (node (ref "C002") (pin "2") (pinfunction "2_2") (pintype "passive"))
      (node (ref "R01") (pin "2") (pinfunction "2_2") (pintype "passive"))
      (node (ref "U01") (pin "6") (pinfunction "OUT_6") (pintype "output"))
    )
    (net (code "34") (name "Net-(U02-IN+)") (class "Default")
      (node (ref "R03") (pin "2") (pinfunction "2_2") (pintype "passive"))
      (node (ref "U02") (pin "3") (pinfunction "IN+_3") (pintype "input"))
    )
    (net (code "35") (name "Net-(U02-IN-)") (class "Default")
      (node (ref "C003") (pin "2") (pinfunction "2_2") (pintype "passive"))
      (node (ref "R04") (pin "2") (pinfunction "2_2") (pintype "passive"))
      (node (ref "R05") (pin "1") (pinfunction "1_1") (pintype "passive"))
      (node (ref "U02") (pin "2") (pinfunction "IN-_2") (pintype "input"))
    )
    (net (code "36") (name "Net-(U03-IN+)") (class "Default")
      (node (ref "R08") (pin "2") (pinfunction "2_2") (pintype "passive"))
      (node (ref "U03") (pin "3") (pinfunction "IN+_3") (pintype "input"))
    )
    (net (code "37") (name "Net-(U03-IN-)") (class "Default")
      (node (ref "C005") (pin "2") (pinfunction "2_2") (pintype "passive"))
      (node (ref "R010") (pin "1") (pinfunction "1_1") (pintype "passive"))
      (node (ref "R09") (pin "2") (pinfunction "2_2") (pintype "passive"))
      (node (ref "U03") (pin "2") (pinfunction "IN-_2") (pintype "input"))
    )
    (net (code "38") (name "Net-(U04-IN+)") (class "Default")
      (node (ref "C007") (pin "1") (pinfunction "1_1") (pintype "passive"))
      (node (ref "R012") (pin "2") (pinfunction "2_2") (pintype "passive"))
      (node (ref "U04") (pin "3") (pinfunction "IN+_3") (pintype "input"))
    )
    (net (code "39") (name "Net-(U04-IN-)") (class "Default")
      (node (ref "R013") (pin "1") (pinfunction "1_1") (pintype "passive"))
      (node (ref "R014") (pin "1") (pinfunction "1_1") (pintype "passive"))
      (node (ref "U04") (pin "2") (pinfunction "IN-_2") (pintype "input"))
      (node (ref "U04") (pin "6") (pinfunction "OUT_6") (pintype "output"))
    )
    (net (code "40") (name "Net-(U05-IN+)") (class "Default")
      (node (ref "C008") (pin "1") (pinfunction "1_1") (pintype "passive"))
      (node (ref "R015") (pin "1") (pinfunction "1_1") (pintype "passive"))
      (node (ref "U05") (pin "3") (pinfunction "IN+_3") (pintype "input"))
    )
    (net (code "41") (name "Net-(U05-IN-)") (class "Default")
      (node (ref "C009") (pin "1") (pinfunction "1_1") (pintype "passive"))
      (node (ref "R016") (pin "1") (pinfunction "1_1") (pintype "passive"))
      (node (ref "U05") (pin "2") (pinfunction "IN-_2") (pintype "input"))
      (node (ref "U05") (pin "6") (pinfunction "OUT_6") (pintype "output"))
    )
    (net (code "42") (name "Net-(U06-IN+)") (class "Default")
      (node (ref "CO10") (pin "2") (pinfunction "2_2") (pintype "passive"))
      (node (ref "R017") (pin "2") (pinfunction "2_2") (pintype "passive"))
      (node (ref "U06") (pin "3") (pinfunction "IN+_3") (pintype "input"))
    )
    (net (code "43") (name "Net-(U06-IN-)") (class "Default")
      (node (ref "CO11") (pin "1") (pinfunction "1_1") (pintype "passive"))
      (node (ref "R018") (pin "1") (pinfunction "1_1") (pintype "passive"))
      (node (ref "U06") (pin "2") (pinfunction "IN-_2") (pintype "input"))
      (node (ref "U06") (pin "6") (pinfunction "OUT_6") (pintype "output"))
    )
    (net (code "44") (name "Net-(U07-IN+)") (class "Default")
      (node (ref "CO12") (pin "2") (pinfunction "2_2") (pintype "passive"))
      (node (ref "R019") (pin "2") (pinfunction "2_2") (pintype "passive"))
      (node (ref "U07") (pin "3") (pinfunction "IN+_3") (pintype "input"))
    )
    (net (code "45") (name "Net-(U08-IN-)") (class "Default")
      (node (ref "C015") (pin "1") (pinfunction "1_1") (pintype "passive"))
      (node (ref "R022") (pin "1") (pinfunction "1_1") (pintype "passive"))
      (node (ref "U08") (pin "2") (pinfunction "IN-_2") (pintype "input"))
    )
    (net (code "46") (name "Net-(U08-OUT)") (class "Default")
      (node (ref "C014") (pin "1") (pinfunction "1_1") (pintype "passive"))
      (node (ref "R022") (pin "2") (pinfunction "2_2") (pintype "passive"))
      (node (ref "R024") (pin "1") (pinfunction "1_1") (pintype "passive"))
      (node (ref "U08") (pin "6") (pinfunction "OUT_6") (pintype "output"))
    )
    (net (code "47") (name "Net-(U09-IN-)") (class "Default")
      (node (ref "C017") (pin "1") (pinfunction "1_1") (pintype "passive"))
      (node (ref "R026") (pin "1") (pinfunction "1_1") (pintype "passive"))
      (node (ref "U09") (pin "2") (pinfunction "IN-_2") (pintype "input"))
    )
    (net (code "48") (name "Net-(U09-OUT)") (class "Default")
      (node (ref "C016") (pin "1") (pinfunction "1_1") (pintype "passive"))
      (node (ref "R026") (pin "2") (pinfunction "2_2") (pintype "passive"))
      (node (ref "R027") (pin "2") (pinfunction "2_2") (pintype "passive"))
      (node (ref "U09") (pin "6") (pinfunction "OUT_6") (pintype "output"))
    )
    (net (code "49") (name "Net-(U011-IN-)") (class "Default")
      (node (ref "C019") (pin "1") (pinfunction "1_1") (pintype "passive"))
      (node (ref "R035") (pin "1") (pinfunction "1_1") (pintype "passive"))
      (node (ref "U011") (pin "2") (pinfunction "IN-_2") (pintype "input"))
    )
    (net (code "50") (name "Net-(U011-OUT)") (class "Default")
      (node (ref "C018") (pin "1") (pinfunction "1_1") (pintype "passive"))
      (node (ref "R035") (pin "2") (pinfunction "2_2") (pintype "passive"))
      (node (ref "R037") (pin "1") (pinfunction "1_1") (pintype "passive"))
      (node (ref "U011") (pin "6") (pinfunction "OUT_6") (pintype "output"))
    )
    (net (code "51") (name "Net-(U012-IN-)") (class "Default")
      (node (ref "C021") (pin "1") (pinfunction "1_1") (pintype "passive"))
      (node (ref "R039") (pin "1") (pinfunction "1_1") (pintype "passive"))
      (node (ref "U012") (pin "2") (pinfunction "IN-_2") (pintype "input"))
    )
    (net (code "52") (name "Net-(U012-OUT)") (class "Default")
      (node (ref "C020") (pin "1") (pinfunction "1_1") (pintype "passive"))
      (node (ref "R039") (pin "2") (pinfunction "2_2") (pintype "passive"))
      (node (ref "R040") (pin "2") (pinfunction "2_2") (pintype "passive"))
      (node (ref "U012") (pin "6") (pinfunction "OUT_6") (pintype "output"))
    )
    (net (code "53") (name "Net-(U014-IN-)") (class "Default")
      (node (ref "C023") (pin "1") (pinfunction "1_1") (pintype "passive"))
      (node (ref "R048") (pin "1") (pinfunction "1_1") (pintype "passive"))
      (node (ref "U014") (pin "2") (pinfunction "IN-_2") (pintype "input"))
    )
    (net (code "54") (name "Net-(U014-OUT)") (class "Default")
      (node (ref "C022") (pin "1") (pinfunction "1_1") (pintype "passive"))
      (node (ref "R048") (pin "2") (pinfunction "2_2") (pintype "passive"))
      (node (ref "R050") (pin "1") (pinfunction "1_1") (pintype "passive"))
      (node (ref "U014") (pin "6") (pinfunction "OUT_6") (pintype "output"))
    )
    (net (code "55") (name "Net-(U015-IN-)") (class "Default")
      (node (ref "C025") (pin "1") (pinfunction "1_1") (pintype "passive"))
      (node (ref "R052") (pin "1") (pinfunction "1_1") (pintype "passive"))
      (node (ref "U015") (pin "2") (pinfunction "IN-_2") (pintype "input"))
    )
    (net (code "56") (name "Net-(U015-OUT)") (class "Default")
      (node (ref "C024") (pin "1") (pinfunction "1_1") (pintype "passive"))
      (node (ref "R052") (pin "2") (pinfunction "2_2") (pintype "passive"))
      (node (ref "R053") (pin "2") (pinfunction "2_2") (pintype "passive"))
      (node (ref "U015") (pin "6") (pinfunction "OUT_6") (pintype "output"))
    )
    (net (code "57") (name "Net-(UB09-IN+)") (class "Default")
      (node (ref "R027") (pin "1") (pinfunction "1_1") (pintype "passive"))
      (node (ref "UB09") (pin "3") (pinfunction "IN+_3") (pintype "input"))
    )
    (net (code "58") (name "Net-(UB09-IN-)") (class "Default")
      (node (ref "C060") (pin "1") (pinfunction "1_1") (pintype "passive"))
      (node (ref "UB09") (pin "2") (pinfunction "IN-_2") (pintype "input"))
      (node (ref "UB09") (pin "6") (pinfunction "OUT_6") (pintype "output"))
    )
    (net (code "59") (name "Net-(UB12-IN+)") (class "Default")
      (node (ref "R040") (pin "1") (pinfunction "1_1") (pintype "passive"))
      (node (ref "UB12") (pin "3") (pinfunction "IN+_3") (pintype "input"))
    )
    (net (code "60") (name "Net-(UB12-IN-)") (class "Default")
      (node (ref "C061") (pin "1") (pinfunction "1_1") (pintype "passive"))
      (node (ref "UB12") (pin "2") (pinfunction "IN-_2") (pintype "input"))
      (node (ref "UB12") (pin "6") (pinfunction "OUT_6") (pintype "output"))
    )
    (net (code "61") (name "Net-(UB15-IN+)") (class "Default")
      (node (ref "R053") (pin "1") (pinfunction "1_1") (pintype "passive"))
      (node (ref "UB15") (pin "3") (pinfunction "IN+_3") (pintype "input"))
    )
    (net (code "62") (name "Net-(UB15-IN-)") (class "Default")
      (node (ref "C062") (pin "1") (pinfunction "1_1") (pintype "passive"))
      (node (ref "UB15") (pin "2") (pinfunction "IN-_2") (pintype "input"))
      (node (ref "UB15") (pin "6") (pinfunction "OUT_6") (pintype "output"))
    )
    (net (code "63") (name "unconnected-(U01-BAL-Pad1)") (class "Default")
      (node (ref "U01") (pin "1") (pinfunction "BAL_1") (pintype "passive+no_connect"))
    )
    (net (code "64") (name "unconnected-(U01-BAL-Pad8)") (class "Default")
      (node (ref "U01") (pin "8") (pinfunction "BAL_8") (pintype "passive+no_connect"))
    )
    (net (code "65") (name "unconnected-(U01-NC-Pad5)") (class "Default")
      (node (ref "U01") (pin "5") (pinfunction "NC_5") (pintype "passive+no_connect"))
    )
    (net (code "66") (name "unconnected-(U02-NC-Pad5)") (class "Default")
      (node (ref "U02") (pin "5") (pinfunction "NC_5") (pintype "passive+no_connect"))
    )
    (net (code "67") (name "unconnected-(U02-VOSTRIM-Pad1)") (class "Default")
      (node (ref "U02") (pin "1") (pinfunction "VOSTRIM_1") (pintype "passive+no_connect"))
    )
    (net (code "68") (name "unconnected-(U02-VOSTRIM-Pad8)") (class "Default")
      (node (ref "U02") (pin "8") (pinfunction "VOSTRIM_8") (pintype "passive+no_connect"))
    )
    (net (code "69") (name "unconnected-(U03-NC-Pad5)") (class "Default")
      (node (ref "U03") (pin "5") (pinfunction "NC_5") (pintype "passive+no_connect"))
    )
    (net (code "70") (name "unconnected-(U03-VOSTRIM-Pad1)") (class "Default")
      (node (ref "U03") (pin "1") (pinfunction "VOSTRIM_1") (pintype "passive+no_connect"))
    )
    (net (code "71") (name "unconnected-(U03-VOSTRIM-Pad8)") (class "Default")
      (node (ref "U03") (pin "8") (pinfunction "VOSTRIM_8") (pintype "passive+no_connect"))
    )
    (net (code "72") (name "unconnected-(U04-NC-Pad5)") (class "Default")
      (node (ref "U04") (pin "5") (pinfunction "NC_5") (pintype "passive+no_connect"))
    )
    (net (code "73") (name "unconnected-(U04-VOSTRIM-Pad1)") (class "Default")
      (node (ref "U04") (pin "1") (pinfunction "VOSTRIM_1") (pintype "passive+no_connect"))
    )
    (net (code "74") (name "unconnected-(U04-VOSTRIM-Pad8)") (class "Default")
      (node (ref "U04") (pin "8") (pinfunction "VOSTRIM_8") (pintype "passive+no_connect"))
    )
    (net (code "75") (name "unconnected-(U05-NC-Pad5)") (class "Default")
      (node (ref "U05") (pin "5") (pinfunction "NC_5") (pintype "passive+no_connect"))
    )
    (net (code "76") (name "unconnected-(U05-VOSTRIM-Pad1)") (class "Default")
      (node (ref "U05") (pin "1") (pinfunction "VOSTRIM_1") (pintype "passive+no_connect"))
    )
    (net (code "77") (name "unconnected-(U05-VOSTRIM-Pad8)") (class "Default")
      (node (ref "U05") (pin "8") (pinfunction "VOSTRIM_8") (pintype "passive+no_connect"))
    )
    (net (code "78") (name "unconnected-(U06-NC-Pad5)") (class "Default")
      (node (ref "U06") (pin "5") (pinfunction "NC_5") (pintype "passive+no_connect"))
    )
    (net (code "79") (name "unconnected-(U06-VOSTRIM-Pad1)") (class "Default")
      (node (ref "U06") (pin "1") (pinfunction "VOSTRIM_1") (pintype "passive+no_connect"))
    )
    (net (code "80") (name "unconnected-(U06-VOSTRIM-Pad8)") (class "Default")
      (node (ref "U06") (pin "8") (pinfunction "VOSTRIM_8") (pintype "passive+no_connect"))
    )
    (net (code "81") (name "unconnected-(U07-NC-Pad5)") (class "Default")
      (node (ref "U07") (pin "5") (pinfunction "NC_5") (pintype "passive+no_connect"))
    )
    (net (code "82") (name "unconnected-(U07-VOSTRIM-Pad1)") (class "Default")
      (node (ref "U07") (pin "1") (pinfunction "VOSTRIM_1") (pintype "passive+no_connect"))
    )
    (net (code "83") (name "unconnected-(U07-VOSTRIM-Pad8)") (class "Default")
      (node (ref "U07") (pin "8") (pinfunction "VOSTRIM_8") (pintype "passive+no_connect"))
    )
    (net (code "84") (name "unconnected-(U08-NC-Pad5)") (class "Default")
      (node (ref "U08") (pin "5") (pinfunction "NC_5") (pintype "passive+no_connect"))
    )
    (net (code "85") (name "unconnected-(U08-VOSTRIM-Pad1)") (class "Default")
      (node (ref "U08") (pin "1") (pinfunction "VOSTRIM_1") (pintype "passive+no_connect"))
    )
    (net (code "86") (name "unconnected-(U08-VOSTRIM-Pad8)") (class "Default")
      (node (ref "U08") (pin "8") (pinfunction "VOSTRIM_8") (pintype "passive+no_connect"))
    )
    (net (code "87") (name "unconnected-(U09-NC-Pad5)") (class "Default")
      (node (ref "U09") (pin "5") (pinfunction "NC_5") (pintype "passive+no_connect"))
    )
    (net (code "88") (name "unconnected-(U09-VOSTRIM-Pad1)") (class "Default")
      (node (ref "U09") (pin "1") (pinfunction "VOSTRIM_1") (pintype "passive+no_connect"))
    )
    (net (code "89") (name "unconnected-(U09-VOSTRIM-Pad8)") (class "Default")
      (node (ref "U09") (pin "8") (pinfunction "VOSTRIM_8") (pintype "passive+no_connect"))
    )
    (net (code "90") (name "unconnected-(U011-NC-Pad5)") (class "Default")
      (node (ref "U011") (pin "5") (pinfunction "NC_5") (pintype "passive+no_connect"))
    )
    (net (code "91") (name "unconnected-(U011-VOSTRIM-Pad1)") (class "Default")
      (node (ref "U011") (pin "1") (pinfunction "VOSTRIM_1") (pintype "passive+no_connect"))
    )
    (net (code "92") (name "unconnected-(U011-VOSTRIM-Pad8)") (class "Default")
      (node (ref "U011") (pin "8") (pinfunction "VOSTRIM_8") (pintype "passive+no_connect"))
    )
    (net (code "93") (name "unconnected-(U012-NC-Pad5)") (class "Default")
      (node (ref "U012") (pin "5") (pinfunction "NC_5") (pintype "passive+no_connect"))
    )
    (net (code "94") (name "unconnected-(U012-VOSTRIM-Pad1)") (class "Default")
      (node (ref "U012") (pin "1") (pinfunction "VOSTRIM_1") (pintype "passive+no_connect"))
    )
    (net (code "95") (name "unconnected-(U012-VOSTRIM-Pad8)") (class "Default")
      (node (ref "U012") (pin "8") (pinfunction "VOSTRIM_8") (pintype "passive+no_connect"))
    )
    (net (code "96") (name "unconnected-(U014-NC-Pad5)") (class "Default")
      (node (ref "U014") (pin "5") (pinfunction "NC_5") (pintype "passive+no_connect"))
    )
    (net (code "97") (name "unconnected-(U014-VOSTRIM-Pad1)") (class "Default")
      (node (ref "U014") (pin "1") (pinfunction "VOSTRIM_1") (pintype "passive+no_connect"))
    )
    (net (code "98") (name "unconnected-(U014-VOSTRIM-Pad8)") (class "Default")
      (node (ref "U014") (pin "8") (pinfunction "VOSTRIM_8") (pintype "passive+no_connect"))
    )
    (net (code "99") (name "unconnected-(U015-NC-Pad5)") (class "Default")
      (node (ref "U015") (pin "5") (pinfunction "NC_5") (pintype "passive+no_connect"))
    )
    (net (code "100") (name "unconnected-(U015-VOSTRIM-Pad1)") (class "Default")
      (node (ref "U015") (pin "1") (pinfunction "VOSTRIM_1") (pintype "passive+no_connect"))
    )
    (net (code "101") (name "unconnected-(U015-VOSTRIM-Pad8)") (class "Default")
      (node (ref "U015") (pin "8") (pinfunction "VOSTRIM_8") (pintype "passive+no_connect"))
    )
    (net (code "102") (name "unconnected-(UB09-NC-Pad5)") (class "Default")
      (node (ref "UB09") (pin "5") (pinfunction "NC_5") (pintype "passive+no_connect"))
    )
    (net (code "103") (name "unconnected-(UB09-VOSTRIM-Pad1)") (class "Default")
      (node (ref "UB09") (pin "1") (pinfunction "VOSTRIM_1") (pintype "passive+no_connect"))
    )
    (net (code "104") (name "unconnected-(UB09-VOSTRIM-Pad8)") (class "Default")
      (node (ref "UB09") (pin "8") (pinfunction "VOSTRIM_8") (pintype "passive+no_connect"))
    )
    (net (code "105") (name "unconnected-(UB12-NC-Pad5)") (class "Default")
      (node (ref "UB12") (pin "5") (pinfunction "NC_5") (pintype "passive+no_connect"))
    )
    (net (code "106") (name "unconnected-(UB12-VOSTRIM-Pad1)") (class "Default")
      (node (ref "UB12") (pin "1") (pinfunction "VOSTRIM_1") (pintype "passive+no_connect"))
    )
    (net (code "107") (name "unconnected-(UB12-VOSTRIM-Pad8)") (class "Default")
      (node (ref "UB12") (pin "8") (pinfunction "VOSTRIM_8") (pintype "passive+no_connect"))
    )
    (net (code "108") (name "unconnected-(UB15-NC-Pad5)") (class "Default")
      (node (ref "UB15") (pin "5") (pinfunction "NC_5") (pintype "passive+no_connect"))
    )
    (net (code "109") (name "unconnected-(UB15-VOSTRIM-Pad1)") (class "Default")
      (node (ref "UB15") (pin "1") (pinfunction "VOSTRIM_1") (pintype "passive+no_connect"))
    )
    (net (code "110") (name "unconnected-(UB15-VOSTRIM-Pad8)") (class "Default")
      (node (ref "UB15") (pin "8") (pinfunction "VOSTRIM_8") (pintype "passive+no_connect"))
    )
  )
)
